# led_RGB.net
KiCad netlist of a schematic drawn in Altium Designer
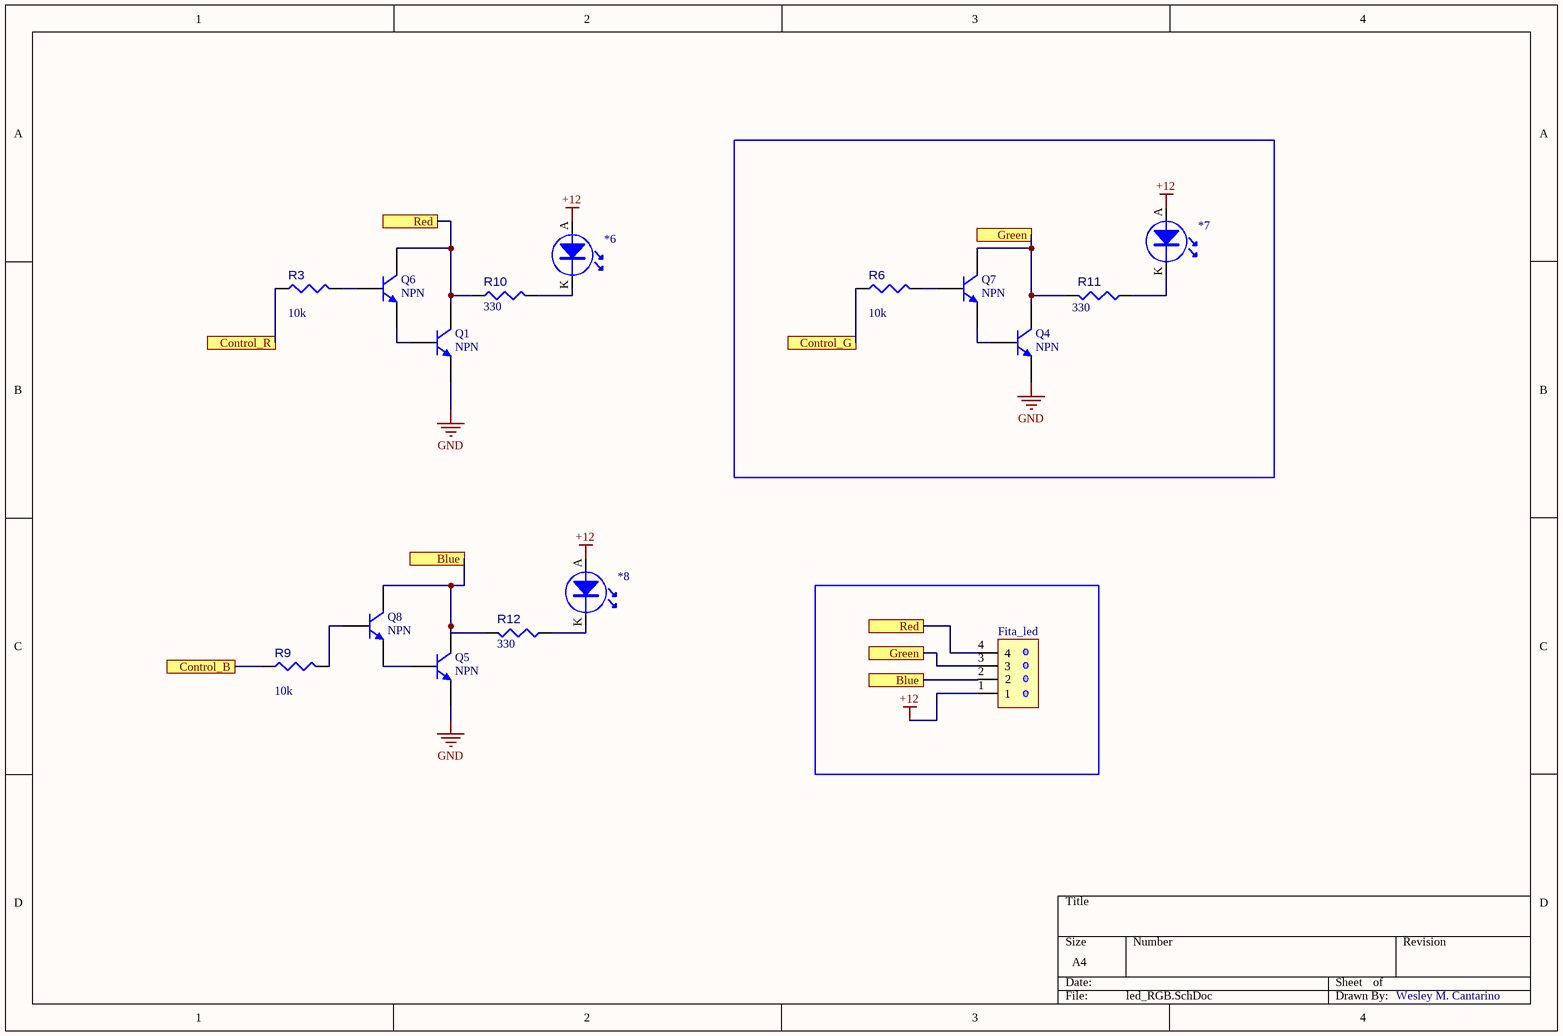
[diagram p0: led_RGB.SchDoc]

(export (version "E")
  (design (tool "Eeschema 10.0.6"))
  (components
    (comp (ref "*6")
      (value "LED_AXIAL_5MM")
      (footprint "HEADER_1X2")
      (libsource (lib "i9Library_Altium") (part "LED_AXIAL_5MM"))
    )
    (comp (ref "*7")
      (value "LED_AXIAL_5MM")
      (footprint "HEADER_1X2")
      (libsource (lib "i9Library_Altium") (part "LED_AXIAL_5MM"))
    )
    (comp (ref "*8")
      (value "LED_AXIAL_5MM")
      (footprint "HEADER_1X2")
      (libsource (lib "i9Library_Altium") (part "LED_AXIAL_5MM"))
    )
    (comp (ref "Fita_led")
      (value "CN_KK_4")
      (footprint "CN_KK_4_5045-4")
      (description "KK_4")
      (libsource (lib "i9Library_Altium") (part "CN_KK_4"))
    )
    (comp (ref "Q1")
      (value "NPN")
      (footprint "HEADER_1X3")
      (description "NPN Bipolar Transistor")
      (fields (field (name "PUBLISHER") "Altium Limited"))
      (libsource (lib "Miscellaneous Devices") (part "NPN"))
    )
    (comp (ref "Q4")
      (value "NPN")
      (footprint "HEADER_1X3")
      (description "NPN Bipolar Transistor")
      (fields (field (name "PUBLISHER") "Altium Limited"))
      (libsource (lib "Miscellaneous Devices") (part "NPN"))
    )
    (comp (ref "Q5")
      (value "NPN")
      (footprint "HEADER_1X3")
      (description "NPN Bipolar Transistor")
      (fields (field (name "PUBLISHER") "Altium Limited"))
      (libsource (lib "Miscellaneous Devices") (part "NPN"))
    )
    (comp (ref "Q6")
      (value "NPN")
      (footprint "HEADER_1X3")
      (description "NPN Bipolar Transistor")
      (fields (field (name "PUBLISHER") "Altium Limited"))
      (libsource (lib "Miscellaneous Devices") (part "NPN"))
    )
    (comp (ref "Q7")
      (value "NPN")
      (footprint "HEADER_1X3")
      (description "NPN Bipolar Transistor")
      (fields (field (name "PUBLISHER") "Altium Limited"))
      (libsource (lib "Miscellaneous Devices") (part "NPN"))
    )
    (comp (ref "Q8")
      (value "NPN")
      (footprint "HEADER_1X3")
      (description "NPN Bipolar Transistor")
      (fields (field (name "PUBLISHER") "Altium Limited"))
      (libsource (lib "Miscellaneous Devices") (part "NPN"))
    )
    (comp (ref "R3")
      (value "10k")
      (footprint "RES_PTH_7.62MM")
      (description "Pin Through Hole Resistor 7.62mm")
      (libsource (lib "i9Library_Altium") (part "RES_PTH_7.62MM"))
    )
    (comp (ref "R6")
      (value "10k")
      (footprint "RES_PTH_7.62MM")
      (description "Pin Through Hole Resistor 7.62mm")
      (libsource (lib "i9Library_Altium") (part "RES_PTH_7.62MM"))
    )
    (comp (ref "R9")
      (value "10k")
      (footprint "RES_PTH_7.62MM")
      (description "Pin Through Hole Resistor 7.62mm")
      (libsource (lib "i9Library_Altium") (part "RES_PTH_7.62MM"))
    )
    (comp (ref "R10")
      (value "330")
      (footprint "RES_PTH_7.62MM")
      (description "Pin Through Hole Resistor 7.62mm")
      (libsource (lib "i9Library_Altium") (part "RES_PTH_7.62MM"))
    )
    (comp (ref "R11")
      (value "330")
      (footprint "RES_PTH_7.62MM")
      (description "Pin Through Hole Resistor 7.62mm")
      (libsource (lib "i9Library_Altium") (part "RES_PTH_7.62MM"))
    )
    (comp (ref "R12")
      (value "330")
      (footprint "RES_PTH_7.62MM")
      (description "Pin Through Hole Resistor 7.62mm")
      (libsource (lib "i9Library_Altium") (part "RES_PTH_7.62MM"))
    )
  )
  (nets
    (net (code "1") (name "+12") (class "Default")
      (node (ref "*6") (pin "A") (pintype "passive"))
      (node (ref "*7") (pin "A") (pintype "passive"))
      (node (ref "*8") (pin "A") (pintype "passive"))
      (node (ref "Fita_led") (pin "1") (pinfunction "1_1") (pintype "passive"))
    )
    (net (code "2") (name "/Blue") (class "Default")
      (node (ref "Fita_led") (pin "2") (pinfunction "2_2") (pintype "passive"))
      (node (ref "Q5") (pin "1") (pinfunction "C_1") (pintype "passive"))
      (node (ref "Q8") (pin "1") (pinfunction "C_1") (pintype "passive"))
      (node (ref "R12") (pin "2") (pinfunction "2_2") (pintype "passive"))
    )
    (net (code "3") (name "/Control_B") (class "Default")
      (node (ref "R9") (pin "1") (pinfunction "1_1") (pintype "passive"))
    )
    (net (code "4") (name "/Control_G") (class "Default")
      (node (ref "R6") (pin "1") (pinfunction "1_1") (pintype "passive"))
    )
    (net (code "5") (name "/Control_R") (class "Default")
      (node (ref "R3") (pin "1") (pinfunction "1_1") (pintype "passive"))
    )
    (net (code "6") (name "/Green") (class "Default")
      (node (ref "Fita_led") (pin "3") (pinfunction "3_3") (pintype "passive"))
      (node (ref "Q4") (pin "1") (pinfunction "C_1") (pintype "passive"))
      (node (ref "Q7") (pin "1") (pinfunction "C_1") (pintype "passive"))
      (node (ref "R11") (pin "2") (pinfunction "2_2") (pintype "passive"))
    )
    (net (code "7") (name "/Red") (class "Default")
      (node (ref "Fita_led") (pin "4") (pinfunction "4_4") (pintype "passive"))
      (node (ref "Q1") (pin "1") (pinfunction "C_1") (pintype "passive"))
      (node (ref "Q6") (pin "1") (pinfunction "C_1") (pintype "passive"))
      (node (ref "R10") (pin "1") (pinfunction "1_1") (pintype "passive"))
    )
    (net (code "8") (name "GND") (class "Default")
      (node (ref "Q1") (pin "3") (pinfunction "E_3") (pintype "passive"))
      (node (ref "Q4") (pin "3") (pinfunction "E_3") (pintype "passive"))
      (node (ref "Q5") (pin "3") (pinfunction "E_3") (pintype "passive"))
    )
    (net (code "9") (name "Net-(*6-PadK)") (class "Default")
      (node (ref "*6") (pin "K") (pintype "passive"))
      (node (ref "R10") (pin "2") (pinfunction "2_2") (pintype "passive"))
    )
    (net (code "10") (name "Net-(*7-PadK)") (class "Default")
      (node (ref "*7") (pin "K") (pintype "passive"))
      (node (ref "R11") (pin "1") (pinfunction "1_1") (pintype "passive"))
    )
    (net (code "11") (name "Net-(*8-PadK)") (class "Default")
      (node (ref "*8") (pin "K") (pintype "passive"))
      (node (ref "R12") (pin "1") (pinfunction "1_1") (pintype "passive"))
    )
    (net (code "12") (name "Net-(Q1-B)") (class "Default")
      (node (ref "Q1") (pin "2") (pinfunction "B_2") (pintype "passive"))
      (node (ref "Q6") (pin "3") (pinfunction "E_3") (pintype "passive"))
    )
    (net (code "13") (name "Net-(Q4-B)") (class "Default")
      (node (ref "Q4") (pin "2") (pinfunction "B_2") (pintype "passive"))
      (node (ref "Q7") (pin "3") (pinfunction "E_3") (pintype "passive"))
    )
    (net (code "14") (name "Net-(Q5-B)") (class "Default")
      (node (ref "Q5") (pin "2") (pinfunction "B_2") (pintype "passive"))
      (node (ref "Q8") (pin "3") (pinfunction "E_3") (pintype "passive"))
    )
    (net (code "15") (name "Net-(Q6-B)") (class "Default")
      (node (ref "Q6") (pin "2") (pinfunction "B_2") (pintype "passive"))
      (node (ref "R3") (pin "2") (pinfunction "2_2") (pintype "passive"))
    )
    (net (code "16") (name "Net-(Q7-B)") (class "Default")
      (node (ref "Q7") (pin "2") (pinfunction "B_2") (pintype "passive"))
      (node (ref "R6") (pin "2") (pinfunction "2_2") (pintype "passive"))
    )
    (net (code "17") (name "Net-(Q8-B)") (class "Default")
      (node (ref "Q8") (pin "2") (pinfunction "B_2") (pintype "passive"))
      (node (ref "R9") (pin "2") (pinfunction "2_2") (pintype "passive"))
    )
  )
)
